# PluggyReloadedEvery.net
KiCad netlist of a schematic drawn in EAGLE
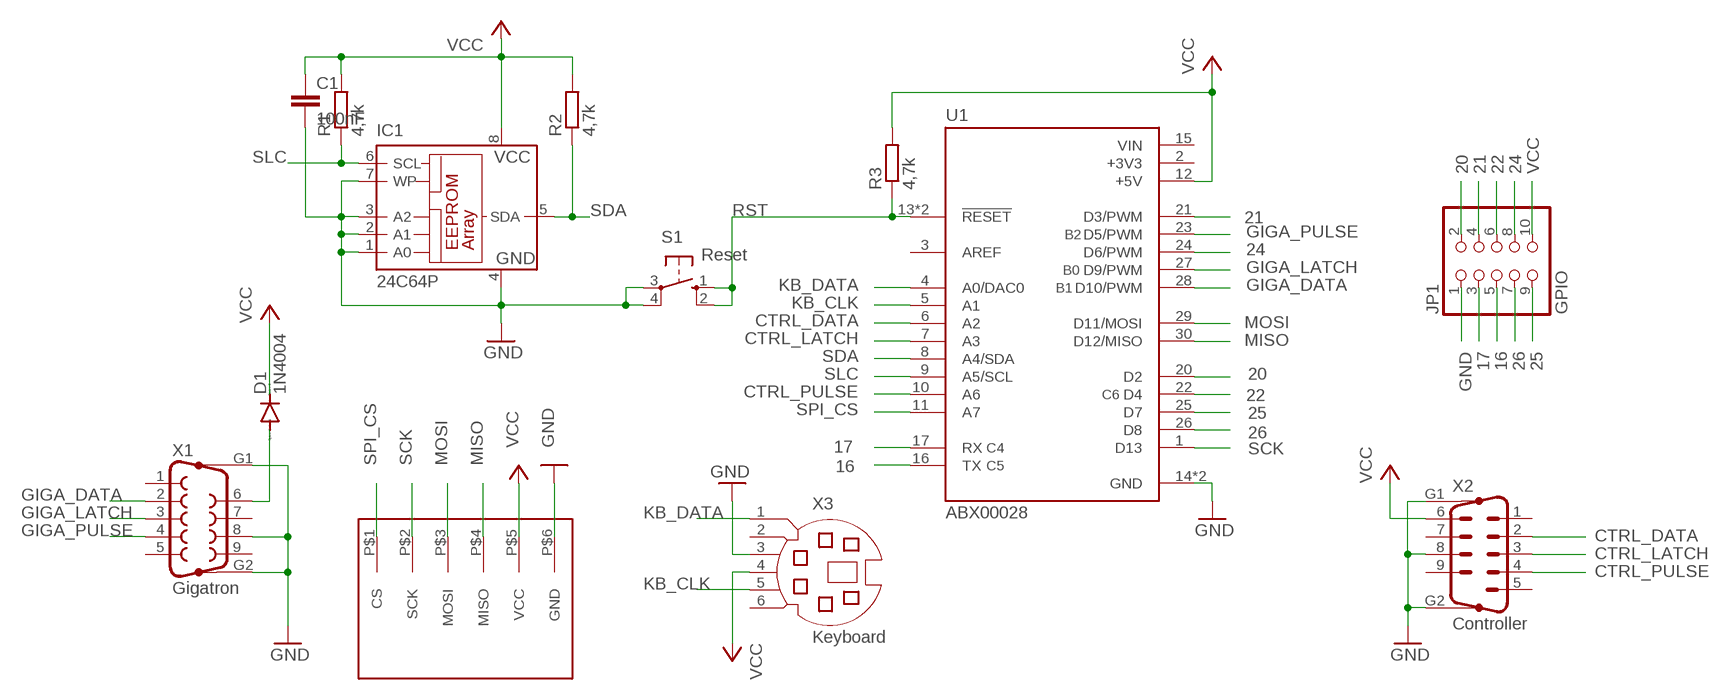
[diagram p0: schematic, sheet 1]

(export (version "E")
  (design (tool "Eeschema 10.0.6"))
  (components
    (comp (ref "C1")
      (value "100nF")
      (footprint "eagle-import:C050-024X044")
      (libsource (lib "eagle-import") (part "C-EU050-024X044"))
    )
    (comp (ref "D1")
      (value "1N4004")
      (footprint "eagle-import:DO41-10")
      (libsource (lib "eagle-import") (part "1N4004"))
    )
    (comp (ref "IC1")
      (value "24C64P")
      (footprint "eagle-import:DIL8")
      (fields (field (name "MF") "RAMTRON INTERNATIONAL CORP") (field (name "MPN") "FM24C64-P"))
      (libsource (lib "eagle-import") (part "24PC64"))
    )
    (comp (ref "JP1")
      (value "GPIO")
      (footprint "eagle-import:2X05")
      (libsource (lib "eagle-import") (part "PINHD-2X5"))
    )
    (comp (ref "R1")
      (value "4,7k")
      (footprint "eagle-import:0207_10")
      (libsource (lib "eagle-import") (part "R-EU_0207/10"))
    )
    (comp (ref "R2")
      (value "4,7k")
      (footprint "eagle-import:0207_10")
      (libsource (lib "eagle-import") (part "R-EU_0207/10"))
    )
    (comp (ref "R3")
      (value "4,7k")
      (footprint "eagle-import:0207_10")
      (libsource (lib "eagle-import") (part "R-EU_0207/10"))
    )
    (comp (ref "S1")
      (value "Reset")
      (footprint "eagle-import:B3F-10XX")
      (fields (field (name "MPN") "B3F-1000"))
      (libsource (lib "eagle-import") (part "10-XX"))
    )
    (comp (ref "U$1")
      (value "BREAKOUT_SD")
      (footprint "eagle-import:BREAKOUT_SD")
      (libsource (lib "eagle-import") (part "BREAKOUT_SD"))
    )
    (comp (ref "U1")
      (value "ABX00028")
      (footprint "eagle-import:MODULE_ABX00028")
      (fields (field (name "MF") "Arduino") (field (name "MP") "Arduino Nano Every"))
      (libsource (lib "eagle-import") (part "ABX00028"))
    )
    (comp (ref "X1")
      (value "Gigatron")
      (footprint "eagle-import:F09HP")
      (libsource (lib "eagle-import") (part "F09HP"))
    )
    (comp (ref "X2")
      (value "Controller")
      (footprint "eagle-import:M09HP")
      (libsource (lib "eagle-import") (part "M09HP"))
    )
    (comp (ref "X3")
      (value "Keyboard")
      (footprint "eagle-import:MDIN06SS")
      (libsource (lib "eagle-import") (part "MD06SS"))
    )
  )
  (nets
    (net (code "1") (name "/+3V3") (class "Default")
      (node (ref "U1") (pin "2") (pinfunction "+3V3_2") (pintype "power_in"))
    )
    (net (code "2") (name "/16") (class "Default")
      (node (ref "JP1") (pin "5") (pinfunction "5_5") (pintype "passive"))
      (node (ref "U1") (pin "16") (pinfunction "TX_16") (pintype "bidirectional"))
    )
    (net (code "3") (name "/17") (class "Default")
      (node (ref "JP1") (pin "3") (pinfunction "3_3") (pintype "passive"))
      (node (ref "U1") (pin "17") (pinfunction "RX_17") (pintype "bidirectional"))
    )
    (net (code "4") (name "/20") (class "Default")
      (node (ref "JP1") (pin "2") (pinfunction "2_2") (pintype "passive"))
      (node (ref "U1") (pin "20") (pinfunction "D2_20") (pintype "bidirectional"))
    )
    (net (code "5") (name "/21") (class "Default")
      (node (ref "JP1") (pin "4") (pinfunction "4_4") (pintype "passive"))
      (node (ref "U1") (pin "21") (pinfunction "D3/PWM_21") (pintype "bidirectional"))
    )
    (net (code "6") (name "/22") (class "Default")
      (node (ref "JP1") (pin "6") (pinfunction "6_6") (pintype "passive"))
      (node (ref "U1") (pin "22") (pinfunction "D4_22") (pintype "bidirectional"))
    )
    (net (code "7") (name "/24") (class "Default")
      (node (ref "JP1") (pin "8") (pinfunction "8_8") (pintype "passive"))
      (node (ref "U1") (pin "24") (pinfunction "D6/PWM_24") (pintype "bidirectional"))
    )
    (net (code "8") (name "/25") (class "Default")
      (node (ref "JP1") (pin "9") (pinfunction "9_9") (pintype "passive"))
      (node (ref "U1") (pin "25") (pinfunction "D7_25") (pintype "bidirectional"))
    )
    (net (code "9") (name "/26") (class "Default")
      (node (ref "JP1") (pin "7") (pinfunction "7_7") (pintype "passive"))
      (node (ref "U1") (pin "26") (pinfunction "D8_26") (pintype "bidirectional"))
    )
    (net (code "10") (name "/CTRL_DATA") (class "Default")
      (node (ref "U1") (pin "6") (pinfunction "A2_6") (pintype "bidirectional"))
      (node (ref "X2") (pin "2") (pinfunction "2_2") (pintype "passive"))
    )
    (net (code "11") (name "/CTRL_LATCH") (class "Default")
      (node (ref "U1") (pin "7") (pinfunction "A3_7") (pintype "bidirectional"))
      (node (ref "X2") (pin "3") (pinfunction "3_3") (pintype "passive"))
    )
    (net (code "12") (name "/CTRL_PULSE") (class "Default")
      (node (ref "U1") (pin "10") (pinfunction "A6_10") (pintype "bidirectional"))
      (node (ref "X2") (pin "4") (pinfunction "4_4") (pintype "passive"))
    )
    (net (code "13") (name "/GIGA_DATA") (class "Default")
      (node (ref "U1") (pin "28") (pinfunction "D10/PWM_28") (pintype "bidirectional"))
      (node (ref "X1") (pin "2") (pinfunction "2_2") (pintype "passive"))
    )
    (net (code "14") (name "/GIGA_LATCH") (class "Default")
      (node (ref "U1") (pin "27") (pinfunction "D9/PWM_27") (pintype "bidirectional"))
      (node (ref "X1") (pin "3") (pinfunction "3_3") (pintype "passive"))
    )
    (net (code "15") (name "/GIGA_PULSE") (class "Default")
      (node (ref "U1") (pin "23") (pinfunction "D5/PWM_23") (pintype "bidirectional"))
      (node (ref "X1") (pin "4") (pinfunction "4_4") (pintype "passive"))
    )
    (net (code "16") (name "/KB_CLK") (class "Default")
      (node (ref "U1") (pin "5") (pinfunction "A1_5") (pintype "bidirectional"))
      (node (ref "X3") (pin "5") (pinfunction "5_5") (pintype "passive"))
    )
    (net (code "17") (name "/KB_DATA") (class "Default")
      (node (ref "U1") (pin "4") (pinfunction "A0/DAC0_4") (pintype "bidirectional"))
      (node (ref "X3") (pin "1") (pinfunction "1_1") (pintype "passive"))
    )
    (net (code "18") (name "/MISO") (class "Default")
      (node (ref "U$1") (pin "P$4") (pinfunction "MISO_P$4") (pintype "bidirectional"))
      (node (ref "U1") (pin "30") (pinfunction "D12/MISO_30") (pintype "bidirectional"))
    )
    (net (code "19") (name "/MOSI") (class "Default")
      (node (ref "U$1") (pin "P$3") (pinfunction "MOSI_P$3") (pintype "bidirectional"))
      (node (ref "U1") (pin "29") (pinfunction "D11/MOSI_29") (pintype "bidirectional"))
    )
    (net (code "20") (name "/RST") (class "Default")
      (node (ref "R3") (pin "1") (pinfunction "1_1") (pintype "passive"))
      (node (ref "S1") (pin "1") (pinfunction "S_1") (pintype "passive"))
      (node (ref "S1") (pin "2") (pinfunction "S1_2") (pintype "passive"))
      (node (ref "U1") (pin "13") (pinfunction "~{RESET}_13") (pintype "input"))
      (node (ref "U1") (pin "18") (pinfunction "~{RESET}_18") (pintype "input"))
    )
    (net (code "21") (name "/SCK") (class "Default")
      (node (ref "U$1") (pin "P$2") (pinfunction "SCK_P$2") (pintype "bidirectional"))
      (node (ref "U1") (pin "1") (pinfunction "D13_1") (pintype "bidirectional"))
    )
    (net (code "22") (name "/SDA") (class "Default")
      (node (ref "IC1") (pin "5") (pinfunction "SDA_5") (pintype "bidirectional"))
      (node (ref "R2") (pin "1") (pinfunction "1_1") (pintype "passive"))
      (node (ref "U1") (pin "8") (pinfunction "A4/SDA_8") (pintype "bidirectional"))
    )
    (net (code "23") (name "/SLC") (class "Default")
      (node (ref "IC1") (pin "6") (pinfunction "SCL_6") (pintype "input"))
      (node (ref "R1") (pin "1") (pinfunction "1_1") (pintype "passive"))
      (node (ref "U1") (pin "9") (pinfunction "A5/SCL_9") (pintype "bidirectional"))
    )
    (net (code "24") (name "/SPI_CS") (class "Default")
      (node (ref "U$1") (pin "P$1") (pinfunction "CS_P$1") (pintype "bidirectional"))
      (node (ref "U1") (pin "11") (pinfunction "A7_11") (pintype "bidirectional"))
    )
    (net (code "25") (name "/VIN") (class "Default")
      (node (ref "U1") (pin "15") (pinfunction "VIN_15") (pintype "power_in"))
    )
    (net (code "26") (name "GND") (class "Default")
      (node (ref "C1") (pin "2") (pinfunction "2_2") (pintype "passive"))
      (node (ref "IC1") (pin "1") (pinfunction "A0_1") (pintype "input"))
      (node (ref "IC1") (pin "2") (pinfunction "A1_2") (pintype "input"))
      (node (ref "IC1") (pin "3") (pinfunction "A2_3") (pintype "input"))
      (node (ref "IC1") (pin "4") (pinfunction "GND_4") (pintype "power_in"))
      (node (ref "IC1") (pin "7") (pinfunction "WP_7") (pintype "input"))
      (node (ref "JP1") (pin "1") (pinfunction "1_1") (pintype "passive"))
      (node (ref "S1") (pin "3") (pinfunction "P_3") (pintype "passive"))
      (node (ref "S1") (pin "4") (pinfunction "P1_4") (pintype "passive"))
      (node (ref "U$1") (pin "P$6") (pinfunction "GND_P$6") (pintype "bidirectional"))
      (node (ref "U1") (pin "14") (pinfunction "GND_14") (pintype "power_in"))
      (node (ref "U1") (pin "19") (pinfunction "GND_19") (pintype "power_in"))
      (node (ref "X1") (pin "8") (pinfunction "8_8") (pintype "passive"))
      (node (ref "X1") (pin "G1") (pinfunction "G1_G1") (pintype "passive"))
      (node (ref "X1") (pin "G2") (pinfunction "G2_G2") (pintype "passive"))
      (node (ref "X2") (pin "8") (pinfunction "8_8") (pintype "passive"))
      (node (ref "X2") (pin "G1") (pinfunction "G1_G1") (pintype "passive"))
      (node (ref "X2") (pin "G2") (pinfunction "G2_G2") (pintype "passive"))
      (node (ref "X3") (pin "3") (pinfunction "3_3") (pintype "passive"))
    )
    (net (code "27") (name "Net-(D1-PadA)") (class "Default")
      (node (ref "D1") (pin "A") (pinfunction "A_A") (pintype "passive"))
      (node (ref "X1") (pin "6") (pinfunction "6_6") (pintype "passive"))
    )
    (net (code "28") (name "VCC") (class "Default")
      (node (ref "C1") (pin "1") (pinfunction "1_1") (pintype "passive"))
      (node (ref "D1") (pin "C") (pinfunction "C_C") (pintype "passive"))
      (node (ref "IC1") (pin "8") (pinfunction "VCC_8") (pintype "power_in"))
      (node (ref "JP1") (pin "10") (pinfunction "10_10") (pintype "passive"))
      (node (ref "R1") (pin "2") (pinfunction "2_2") (pintype "passive"))
      (node (ref "R2") (pin "2") (pinfunction "2_2") (pintype "passive"))
      (node (ref "R3") (pin "2") (pinfunction "2_2") (pintype "passive"))
      (node (ref "U$1") (pin "P$5") (pinfunction "VCC_P$5") (pintype "bidirectional"))
      (node (ref "U1") (pin "12") (pinfunction "+5V_12") (pintype "power_in"))
      (node (ref "X2") (pin "6") (pinfunction "6_6") (pintype "passive"))
      (node (ref "X3") (pin "4") (pinfunction "4_4") (pintype "passive"))
    )
    (net (code "29") (name "unconnected-(U1-AREF-Pad3)") (class "Default")
      (node (ref "U1") (pin "3") (pinfunction "AREF_3") (pintype "bidirectional"))
    )
    (net (code "30") (name "unconnected-(X1-Pad1)") (class "Default")
      (node (ref "X1") (pin "1") (pinfunction "1_1") (pintype "passive"))
    )
    (net (code "31") (name "unconnected-(X1-Pad5)") (class "Default")
      (node (ref "X1") (pin "5") (pinfunction "5_5") (pintype "passive"))
    )
    (net (code "32") (name "unconnected-(X1-Pad7)") (class "Default")
      (node (ref "X1") (pin "7") (pinfunction "7_7") (pintype "passive"))
    )
    (net (code "33") (name "unconnected-(X1-Pad9)") (class "Default")
      (node (ref "X1") (pin "9") (pinfunction "9_9") (pintype "passive"))
    )
    (net (code "34") (name "unconnected-(X2-Pad1)") (class "Default")
      (node (ref "X2") (pin "1") (pinfunction "1_1") (pintype "passive"))
    )
    (net (code "35") (name "unconnected-(X2-Pad5)") (class "Default")
      (node (ref "X2") (pin "5") (pinfunction "5_5") (pintype "passive"))
    )
    (net (code "36") (name "unconnected-(X2-Pad7)") (class "Default")
      (node (ref "X2") (pin "7") (pinfunction "7_7") (pintype "passive"))
    )
    (net (code "37") (name "unconnected-(X2-Pad9)") (class "Default")
      (node (ref "X2") (pin "9") (pinfunction "9_9") (pintype "passive"))
    )
    (net (code "38") (name "unconnected-(X3-Pad2)") (class "Default")
      (node (ref "X3") (pin "2") (pinfunction "2_2") (pintype "passive"))
    )
    (net (code "39") (name "unconnected-(X3-Pad6)") (class "Default")
      (node (ref "X3") (pin "6") (pinfunction "6_6") (pintype "passive"))
    )
  )
)
